# PDT3535LEDbackup.net
KiCad netlist of a schematic drawn in EAGLE
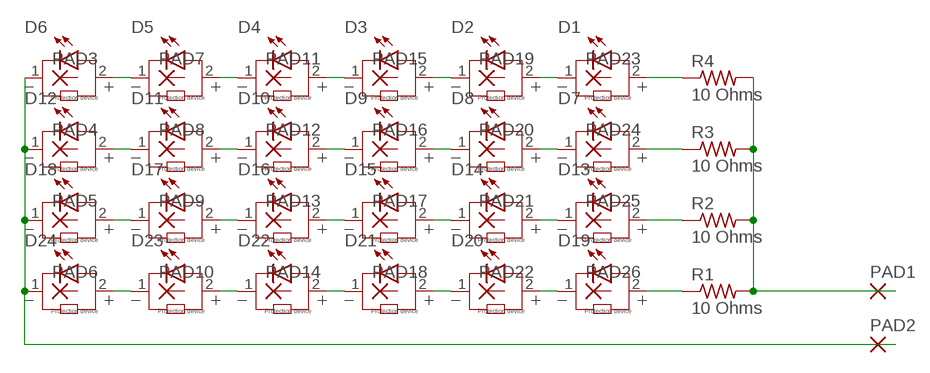
[diagram p0: schematic, sheet 1]

(export (version "E")
  (design (tool "Eeschema 10.0.6"))
  (components
    (comp (ref "D1")
      (value "WL-SWTC_3535_158353060_6000K")
      (footprint "eagle-import:WL-SWTC_3535")
      (libsource (lib "eagle-import") (part "WL-SWTC_3535_158353060_6000K"))
    )
    (comp (ref "D2")
      (value "WL-SWTC_3535_158353060_6000K")
      (footprint "eagle-import:WL-SWTC_3535")
      (libsource (lib "eagle-import") (part "WL-SWTC_3535_158353060_6000K"))
    )
    (comp (ref "D3")
      (value "WL-SWTC_3535_158353060_6000K")
      (footprint "eagle-import:WL-SWTC_3535")
      (libsource (lib "eagle-import") (part "WL-SWTC_3535_158353060_6000K"))
    )
    (comp (ref "D4")
      (value "WL-SWTC_3535_158353060_6000K")
      (footprint "eagle-import:WL-SWTC_3535")
      (libsource (lib "eagle-import") (part "WL-SWTC_3535_158353060_6000K"))
    )
    (comp (ref "D5")
      (value "WL-SWTC_3535_158353060_6000K")
      (footprint "eagle-import:WL-SWTC_3535")
      (libsource (lib "eagle-import") (part "WL-SWTC_3535_158353060_6000K"))
    )
    (comp (ref "D6")
      (value "WL-SWTC_3535_158353060_6000K")
      (footprint "eagle-import:WL-SWTC_3535")
      (libsource (lib "eagle-import") (part "WL-SWTC_3535_158353060_6000K"))
    )
    (comp (ref "D7")
      (value "WL-SWTC_3535_158353060_6000K")
      (footprint "eagle-import:WL-SWTC_3535")
      (libsource (lib "eagle-import") (part "WL-SWTC_3535_158353060_6000K"))
    )
    (comp (ref "D8")
      (value "WL-SWTC_3535_158353060_6000K")
      (footprint "eagle-import:WL-SWTC_3535")
      (libsource (lib "eagle-import") (part "WL-SWTC_3535_158353060_6000K"))
    )
    (comp (ref "D9")
      (value "WL-SWTC_3535_158353060_6000K")
      (footprint "eagle-import:WL-SWTC_3535")
      (libsource (lib "eagle-import") (part "WL-SWTC_3535_158353060_6000K"))
    )
    (comp (ref "D10")
      (value "WL-SWTC_3535_158353060_6000K")
      (footprint "eagle-import:WL-SWTC_3535")
      (libsource (lib "eagle-import") (part "WL-SWTC_3535_158353060_6000K"))
    )
    (comp (ref "D11")
      (value "WL-SWTC_3535_158353060_6000K")
      (footprint "eagle-import:WL-SWTC_3535")
      (libsource (lib "eagle-import") (part "WL-SWTC_3535_158353060_6000K"))
    )
    (comp (ref "D12")
      (value "WL-SWTC_3535_158353060_6000K")
      (footprint "eagle-import:WL-SWTC_3535")
      (libsource (lib "eagle-import") (part "WL-SWTC_3535_158353060_6000K"))
    )
    (comp (ref "D13")
      (value "WL-SWTC_3535_158353060_6000K")
      (footprint "eagle-import:WL-SWTC_3535")
      (libsource (lib "eagle-import") (part "WL-SWTC_3535_158353060_6000K"))
    )
    (comp (ref "D14")
      (value "WL-SWTC_3535_158353060_6000K")
      (footprint "eagle-import:WL-SWTC_3535")
      (libsource (lib "eagle-import") (part "WL-SWTC_3535_158353060_6000K"))
    )
    (comp (ref "D15")
      (value "WL-SWTC_3535_158353060_6000K")
      (footprint "eagle-import:WL-SWTC_3535")
      (libsource (lib "eagle-import") (part "WL-SWTC_3535_158353060_6000K"))
    )
    (comp (ref "D16")
      (value "WL-SWTC_3535_158353060_6000K")
      (footprint "eagle-import:WL-SWTC_3535")
      (libsource (lib "eagle-import") (part "WL-SWTC_3535_158353060_6000K"))
    )
    (comp (ref "D17")
      (value "WL-SWTC_3535_158353060_6000K")
      (footprint "eagle-import:WL-SWTC_3535")
      (libsource (lib "eagle-import") (part "WL-SWTC_3535_158353060_6000K"))
    )
    (comp (ref "D18")
      (value "WL-SWTC_3535_158353060_6000K")
      (footprint "eagle-import:WL-SWTC_3535")
      (libsource (lib "eagle-import") (part "WL-SWTC_3535_158353060_6000K"))
    )
    (comp (ref "D19")
      (value "WL-SWTC_3535_158353060_6000K")
      (footprint "eagle-import:WL-SWTC_3535")
      (libsource (lib "eagle-import") (part "WL-SWTC_3535_158353060_6000K"))
    )
    (comp (ref "D20")
      (value "WL-SWTC_3535_158353060_6000K")
      (footprint "eagle-import:WL-SWTC_3535")
      (libsource (lib "eagle-import") (part "WL-SWTC_3535_158353060_6000K"))
    )
    (comp (ref "D21")
      (value "WL-SWTC_3535_158353060_6000K")
      (footprint "eagle-import:WL-SWTC_3535")
      (libsource (lib "eagle-import") (part "WL-SWTC_3535_158353060_6000K"))
    )
    (comp (ref "D22")
      (value "WL-SWTC_3535_158353060_6000K")
      (footprint "eagle-import:WL-SWTC_3535")
      (libsource (lib "eagle-import") (part "WL-SWTC_3535_158353060_6000K"))
    )
    (comp (ref "D23")
      (value "WL-SWTC_3535_158353060_6000K")
      (footprint "eagle-import:WL-SWTC_3535")
      (libsource (lib "eagle-import") (part "WL-SWTC_3535_158353060_6000K"))
    )
    (comp (ref "D24")
      (value "WL-SWTC_3535_158353060_6000K")
      (footprint "eagle-import:WL-SWTC_3535")
      (libsource (lib "eagle-import") (part "WL-SWTC_3535_158353060_6000K"))
    )
    (comp (ref "PAD1")
      (value "1,6/0,8")
      (footprint "eagle-import:1,6_0,8")
      (libsource (lib "eagle-import") (part "1,6/0,8"))
    )
    (comp (ref "PAD2")
      (value "1,6/0,8")
      (footprint "eagle-import:1,6_0,8")
      (libsource (lib "eagle-import") (part "1,6/0,8"))
    )
    (comp (ref "PAD3")
      (value "2,54/1,1")
      (footprint "eagle-import:2,54_1,1")
      (libsource (lib "eagle-import") (part "2,54/1,1"))
    )
    (comp (ref "PAD4")
      (value "2,54/1,1")
      (footprint "eagle-import:2,54_1,1")
      (libsource (lib "eagle-import") (part "2,54/1,1"))
    )
    (comp (ref "PAD5")
      (value "2,54/1,1")
      (footprint "eagle-import:2,54_1,1")
      (libsource (lib "eagle-import") (part "2,54/1,1"))
    )
    (comp (ref "PAD6")
      (value "2,54/1,1")
      (footprint "eagle-import:2,54_1,1")
      (libsource (lib "eagle-import") (part "2,54/1,1"))
    )
    (comp (ref "PAD7")
      (value "2,54/1,1")
      (footprint "eagle-import:2,54_1,1")
      (libsource (lib "eagle-import") (part "2,54/1,1"))
    )
    (comp (ref "PAD8")
      (value "2,54/1,1")
      (footprint "eagle-import:2,54_1,1")
      (libsource (lib "eagle-import") (part "2,54/1,1"))
    )
    (comp (ref "PAD9")
      (value "2,54/1,1")
      (footprint "eagle-import:2,54_1,1")
      (libsource (lib "eagle-import") (part "2,54/1,1"))
    )
    (comp (ref "PAD10")
      (value "2,54/1,1")
      (footprint "eagle-import:2,54_1,1")
      (libsource (lib "eagle-import") (part "2,54/1,1"))
    )
    (comp (ref "PAD11")
      (value "2,54/1,1")
      (footprint "eagle-import:2,54_1,1")
      (libsource (lib "eagle-import") (part "2,54/1,1"))
    )
    (comp (ref "PAD12")
      (value "2,54/1,1")
      (footprint "eagle-import:2,54_1,1")
      (libsource (lib "eagle-import") (part "2,54/1,1"))
    )
    (comp (ref "PAD13")
      (value "2,54/1,1")
      (footprint "eagle-import:2,54_1,1")
      (libsource (lib "eagle-import") (part "2,54/1,1"))
    )
    (comp (ref "PAD14")
      (value "2,54/1,1")
      (footprint "eagle-import:2,54_1,1")
      (libsource (lib "eagle-import") (part "2,54/1,1"))
    )
    (comp (ref "PAD15")
      (value "2,54/1,1")
      (footprint "eagle-import:2,54_1,1")
      (libsource (lib "eagle-import") (part "2,54/1,1"))
    )
    (comp (ref "PAD16")
      (value "2,54/1,1")
      (footprint "eagle-import:2,54_1,1")
      (libsource (lib "eagle-import") (part "2,54/1,1"))
    )
    (comp (ref "PAD17")
      (value "2,54/1,1")
      (footprint "eagle-import:2,54_1,1")
      (libsource (lib "eagle-import") (part "2,54/1,1"))
    )
    (comp (ref "PAD18")
      (value "2,54/1,1")
      (footprint "eagle-import:2,54_1,1")
      (libsource (lib "eagle-import") (part "2,54/1,1"))
    )
    (comp (ref "PAD19")
      (value "2,54/1,1")
      (footprint "eagle-import:2,54_1,1")
      (libsource (lib "eagle-import") (part "2,54/1,1"))
    )
    (comp (ref "PAD20")
      (value "2,54/1,1")
      (footprint "eagle-import:2,54_1,1")
      (libsource (lib "eagle-import") (part "2,54/1,1"))
    )
    (comp (ref "PAD21")
      (value "2,54/1,1")
      (footprint "eagle-import:2,54_1,1")
      (libsource (lib "eagle-import") (part "2,54/1,1"))
    )
    (comp (ref "PAD22")
      (value "2,54/1,1")
      (footprint "eagle-import:2,54_1,1")
      (libsource (lib "eagle-import") (part "2,54/1,1"))
    )
    (comp (ref "PAD23")
      (value "2,54/1,1")
      (footprint "eagle-import:2,54_1,1")
      (libsource (lib "eagle-import") (part "2,54/1,1"))
    )
    (comp (ref "PAD24")
      (value "2,54/1,1")
      (footprint "eagle-import:2,54_1,1")
      (libsource (lib "eagle-import") (part "2,54/1,1"))
    )
    (comp (ref "PAD25")
      (value "2,54/1,1")
      (footprint "eagle-import:2,54_1,1")
      (libsource (lib "eagle-import") (part "2,54/1,1"))
    )
    (comp (ref "PAD26")
      (value "2,54/1,1")
      (footprint "eagle-import:2,54_1,1")
      (libsource (lib "eagle-import") (part "2,54/1,1"))
    )
    (comp (ref "R1")
      (value "10 Ohms")
      (footprint "eagle-import:0617_22")
      (libsource (lib "eagle-import") (part "R-US_0617/22"))
    )
    (comp (ref "R2")
      (value "10 Ohms")
      (footprint "eagle-import:0617_22")
      (libsource (lib "eagle-import") (part "R-US_0617/22"))
    )
    (comp (ref "R3")
      (value "10 Ohms")
      (footprint "eagle-import:0617_22")
      (libsource (lib "eagle-import") (part "R-US_0617/22"))
    )
    (comp (ref "R4")
      (value "10 Ohms")
      (footprint "eagle-import:0617_22")
      (libsource (lib "eagle-import") (part "R-US_0617/22"))
    )
  )
  (nets
    (net (code "1") (name "Net-(D1-Pad1)") (class "Default")
      (node (ref "D1") (pin "1") (pinfunction "1_1") (pintype "passive"))
      (node (ref "D2") (pin "2") (pinfunction "2_2") (pintype "passive"))
    )
    (net (code "2") (name "Net-(D1-Pad2)") (class "Default")
      (node (ref "D1") (pin "2") (pinfunction "2_2") (pintype "passive"))
      (node (ref "R4") (pin "1") (pinfunction "1_1") (pintype "passive"))
    )
    (net (code "3") (name "Net-(D2-Pad1)") (class "Default")
      (node (ref "D2") (pin "1") (pinfunction "1_1") (pintype "passive"))
      (node (ref "D3") (pin "2") (pinfunction "2_2") (pintype "passive"))
    )
    (net (code "4") (name "Net-(D3-Pad1)") (class "Default")
      (node (ref "D3") (pin "1") (pinfunction "1_1") (pintype "passive"))
      (node (ref "D4") (pin "2") (pinfunction "2_2") (pintype "passive"))
    )
    (net (code "5") (name "Net-(D4-Pad1)") (class "Default")
      (node (ref "D4") (pin "1") (pinfunction "1_1") (pintype "passive"))
      (node (ref "D5") (pin "2") (pinfunction "2_2") (pintype "passive"))
    )
    (net (code "6") (name "Net-(D5-Pad1)") (class "Default")
      (node (ref "D5") (pin "1") (pinfunction "1_1") (pintype "passive"))
      (node (ref "D6") (pin "2") (pinfunction "2_2") (pintype "passive"))
    )
    (net (code "7") (name "Net-(D7-Pad1)") (class "Default")
      (node (ref "D7") (pin "1") (pinfunction "1_1") (pintype "passive"))
      (node (ref "D8") (pin "2") (pinfunction "2_2") (pintype "passive"))
    )
    (net (code "8") (name "Net-(D7-Pad2)") (class "Default")
      (node (ref "D7") (pin "2") (pinfunction "2_2") (pintype "passive"))
      (node (ref "R3") (pin "1") (pinfunction "1_1") (pintype "passive"))
    )
    (net (code "9") (name "Net-(D8-Pad1)") (class "Default")
      (node (ref "D8") (pin "1") (pinfunction "1_1") (pintype "passive"))
      (node (ref "D9") (pin "2") (pinfunction "2_2") (pintype "passive"))
    )
    (net (code "10") (name "Net-(D10-Pad1)") (class "Default")
      (node (ref "D10") (pin "1") (pinfunction "1_1") (pintype "passive"))
      (node (ref "D11") (pin "2") (pinfunction "2_2") (pintype "passive"))
    )
    (net (code "11") (name "Net-(D10-Pad2)") (class "Default")
      (node (ref "D10") (pin "2") (pinfunction "2_2") (pintype "passive"))
      (node (ref "D9") (pin "1") (pinfunction "1_1") (pintype "passive"))
    )
    (net (code "12") (name "Net-(D11-Pad1)") (class "Default")
      (node (ref "D11") (pin "1") (pinfunction "1_1") (pintype "passive"))
      (node (ref "D12") (pin "2") (pinfunction "2_2") (pintype "passive"))
    )
    (net (code "13") (name "Net-(D13-Pad1)") (class "Default")
      (node (ref "D13") (pin "1") (pinfunction "1_1") (pintype "passive"))
      (node (ref "D14") (pin "2") (pinfunction "2_2") (pintype "passive"))
    )
    (net (code "14") (name "Net-(D13-Pad2)") (class "Default")
      (node (ref "D13") (pin "2") (pinfunction "2_2") (pintype "passive"))
      (node (ref "R2") (pin "1") (pinfunction "1_1") (pintype "passive"))
    )
    (net (code "15") (name "Net-(D14-Pad1)") (class "Default")
      (node (ref "D14") (pin "1") (pinfunction "1_1") (pintype "passive"))
      (node (ref "D15") (pin "2") (pinfunction "2_2") (pintype "passive"))
    )
    (net (code "16") (name "Net-(D15-Pad1)") (class "Default")
      (node (ref "D15") (pin "1") (pinfunction "1_1") (pintype "passive"))
      (node (ref "D16") (pin "2") (pinfunction "2_2") (pintype "passive"))
    )
    (net (code "17") (name "Net-(D16-Pad1)") (class "Default")
      (node (ref "D16") (pin "1") (pinfunction "1_1") (pintype "passive"))
      (node (ref "D17") (pin "2") (pinfunction "2_2") (pintype "passive"))
    )
    (net (code "18") (name "Net-(D17-Pad1)") (class "Default")
      (node (ref "D17") (pin "1") (pinfunction "1_1") (pintype "passive"))
      (node (ref "D18") (pin "2") (pinfunction "2_2") (pintype "passive"))
    )
    (net (code "19") (name "Net-(D19-Pad1)") (class "Default")
      (node (ref "D19") (pin "1") (pinfunction "1_1") (pintype "passive"))
      (node (ref "D20") (pin "2") (pinfunction "2_2") (pintype "passive"))
    )
    (net (code "20") (name "Net-(D19-Pad2)") (class "Default")
      (node (ref "D19") (pin "2") (pinfunction "2_2") (pintype "passive"))
      (node (ref "R1") (pin "1") (pinfunction "1_1") (pintype "passive"))
    )
    (net (code "21") (name "Net-(D20-Pad1)") (class "Default")
      (node (ref "D20") (pin "1") (pinfunction "1_1") (pintype "passive"))
      (node (ref "D21") (pin "2") (pinfunction "2_2") (pintype "passive"))
    )
    (net (code "22") (name "Net-(D21-Pad1)") (class "Default")
      (node (ref "D21") (pin "1") (pinfunction "1_1") (pintype "passive"))
      (node (ref "D22") (pin "2") (pinfunction "2_2") (pintype "passive"))
    )
    (net (code "23") (name "Net-(D22-Pad1)") (class "Default")
      (node (ref "D22") (pin "1") (pinfunction "1_1") (pintype "passive"))
      (node (ref "D23") (pin "2") (pinfunction "2_2") (pintype "passive"))
    )
    (net (code "24") (name "Net-(D23-Pad1)") (class "Default")
      (node (ref "D23") (pin "1") (pinfunction "1_1") (pintype "passive"))
      (node (ref "D24") (pin "2") (pinfunction "2_2") (pintype "passive"))
    )
    (net (code "25") (name "Net-(PAD1-P)") (class "Default")
      (node (ref "PAD1") (pin "1") (pinfunction "P_1") (pintype "passive"))
      (node (ref "R1") (pin "2") (pinfunction "2_2") (pintype "passive"))
      (node (ref "R2") (pin "2") (pinfunction "2_2") (pintype "passive"))
      (node (ref "R3") (pin "2") (pinfunction "2_2") (pintype "passive"))
      (node (ref "R4") (pin "2") (pinfunction "2_2") (pintype "passive"))
    )
    (net (code "26") (name "Net-(PAD2-P)") (class "Default")
      (node (ref "D12") (pin "1") (pinfunction "1_1") (pintype "passive"))
      (node (ref "D18") (pin "1") (pinfunction "1_1") (pintype "passive"))
      (node (ref "D24") (pin "1") (pinfunction "1_1") (pintype "passive"))
      (node (ref "D6") (pin "1") (pinfunction "1_1") (pintype "passive"))
      (node (ref "PAD2") (pin "1") (pinfunction "P_1") (pintype "passive"))
    )
    (net (code "27") (name "unconnected-(PAD3-P-Pad1)") (class "Default")
      (node (ref "PAD3") (pin "1") (pinfunction "P_1") (pintype "passive"))
    )
    (net (code "28") (name "unconnected-(PAD4-P-Pad1)") (class "Default")
      (node (ref "PAD4") (pin "1") (pinfunction "P_1") (pintype "passive"))
    )
    (net (code "29") (name "unconnected-(PAD5-P-Pad1)") (class "Default")
      (node (ref "PAD5") (pin "1") (pinfunction "P_1") (pintype "passive"))
    )
    (net (code "30") (name "unconnected-(PAD6-P-Pad1)") (class "Default")
      (node (ref "PAD6") (pin "1") (pinfunction "P_1") (pintype "passive"))
    )
    (net (code "31") (name "unconnected-(PAD7-P-Pad1)") (class "Default")
      (node (ref "PAD7") (pin "1") (pinfunction "P_1") (pintype "passive"))
    )
    (net (code "32") (name "unconnected-(PAD8-P-Pad1)") (class "Default")
      (node (ref "PAD8") (pin "1") (pinfunction "P_1") (pintype "passive"))
    )
    (net (code "33") (name "unconnected-(PAD9-P-Pad1)") (class "Default")
      (node (ref "PAD9") (pin "1") (pinfunction "P_1") (pintype "passive"))
    )
    (net (code "34") (name "unconnected-(PAD10-P-Pad1)") (class "Default")
      (node (ref "PAD10") (pin "1") (pinfunction "P_1") (pintype "passive"))
    )
    (net (code "35") (name "unconnected-(PAD11-P-Pad1)") (class "Default")
      (node (ref "PAD11") (pin "1") (pinfunction "P_1") (pintype "passive"))
    )
    (net (code "36") (name "unconnected-(PAD12-P-Pad1)") (class "Default")
      (node (ref "PAD12") (pin "1") (pinfunction "P_1") (pintype "passive"))
    )
    (net (code "37") (name "unconnected-(PAD13-P-Pad1)") (class "Default")
      (node (ref "PAD13") (pin "1") (pinfunction "P_1") (pintype "passive"))
    )
    (net (code "38") (name "unconnected-(PAD14-P-Pad1)") (class "Default")
      (node (ref "PAD14") (pin "1") (pinfunction "P_1") (pintype "passive"))
    )
    (net (code "39") (name "unconnected-(PAD15-P-Pad1)") (class "Default")
      (node (ref "PAD15") (pin "1") (pinfunction "P_1") (pintype "passive"))
    )
    (net (code "40") (name "unconnected-(PAD16-P-Pad1)") (class "Default")
      (node (ref "PAD16") (pin "1") (pinfunction "P_1") (pintype "passive"))
    )
    (net (code "41") (name "unconnected-(PAD17-P-Pad1)") (class "Default")
      (node (ref "PAD17") (pin "1") (pinfunction "P_1") (pintype "passive"))
    )
    (net (code "42") (name "unconnected-(PAD18-P-Pad1)") (class "Default")
      (node (ref "PAD18") (pin "1") (pinfunction "P_1") (pintype "passive"))
    )
    (net (code "43") (name "unconnected-(PAD19-P-Pad1)") (class "Default")
      (node (ref "PAD19") (pin "1") (pinfunction "P_1") (pintype "passive"))
    )
    (net (code "44") (name "unconnected-(PAD20-P-Pad1)") (class "Default")
      (node (ref "PAD20") (pin "1") (pinfunction "P_1") (pintype "passive"))
    )
    (net (code "45") (name "unconnected-(PAD21-P-Pad1)") (class "Default")
      (node (ref "PAD21") (pin "1") (pinfunction "P_1") (pintype "passive"))
    )
    (net (code "46") (name "unconnected-(PAD22-P-Pad1)") (class "Default")
      (node (ref "PAD22") (pin "1") (pinfunction "P_1") (pintype "passive"))
    )
    (net (code "47") (name "unconnected-(PAD23-P-Pad1)") (class "Default")
      (node (ref "PAD23") (pin "1") (pinfunction "P_1") (pintype "passive"))
    )
    (net (code "48") (name "unconnected-(PAD24-P-Pad1)") (class "Default")
      (node (ref "PAD24") (pin "1") (pinfunction "P_1") (pintype "passive"))
    )
    (net (code "49") (name "unconnected-(PAD25-P-Pad1)") (class "Default")
      (node (ref "PAD25") (pin "1") (pinfunction "P_1") (pintype "passive"))
    )
    (net (code "50") (name "unconnected-(PAD26-P-Pad1)") (class "Default")
      (node (ref "PAD26") (pin "1") (pinfunction "P_1") (pintype "passive"))
    )
  )
)
